# LEDs.net
KiCad netlist of a schematic drawn in Altium Designer
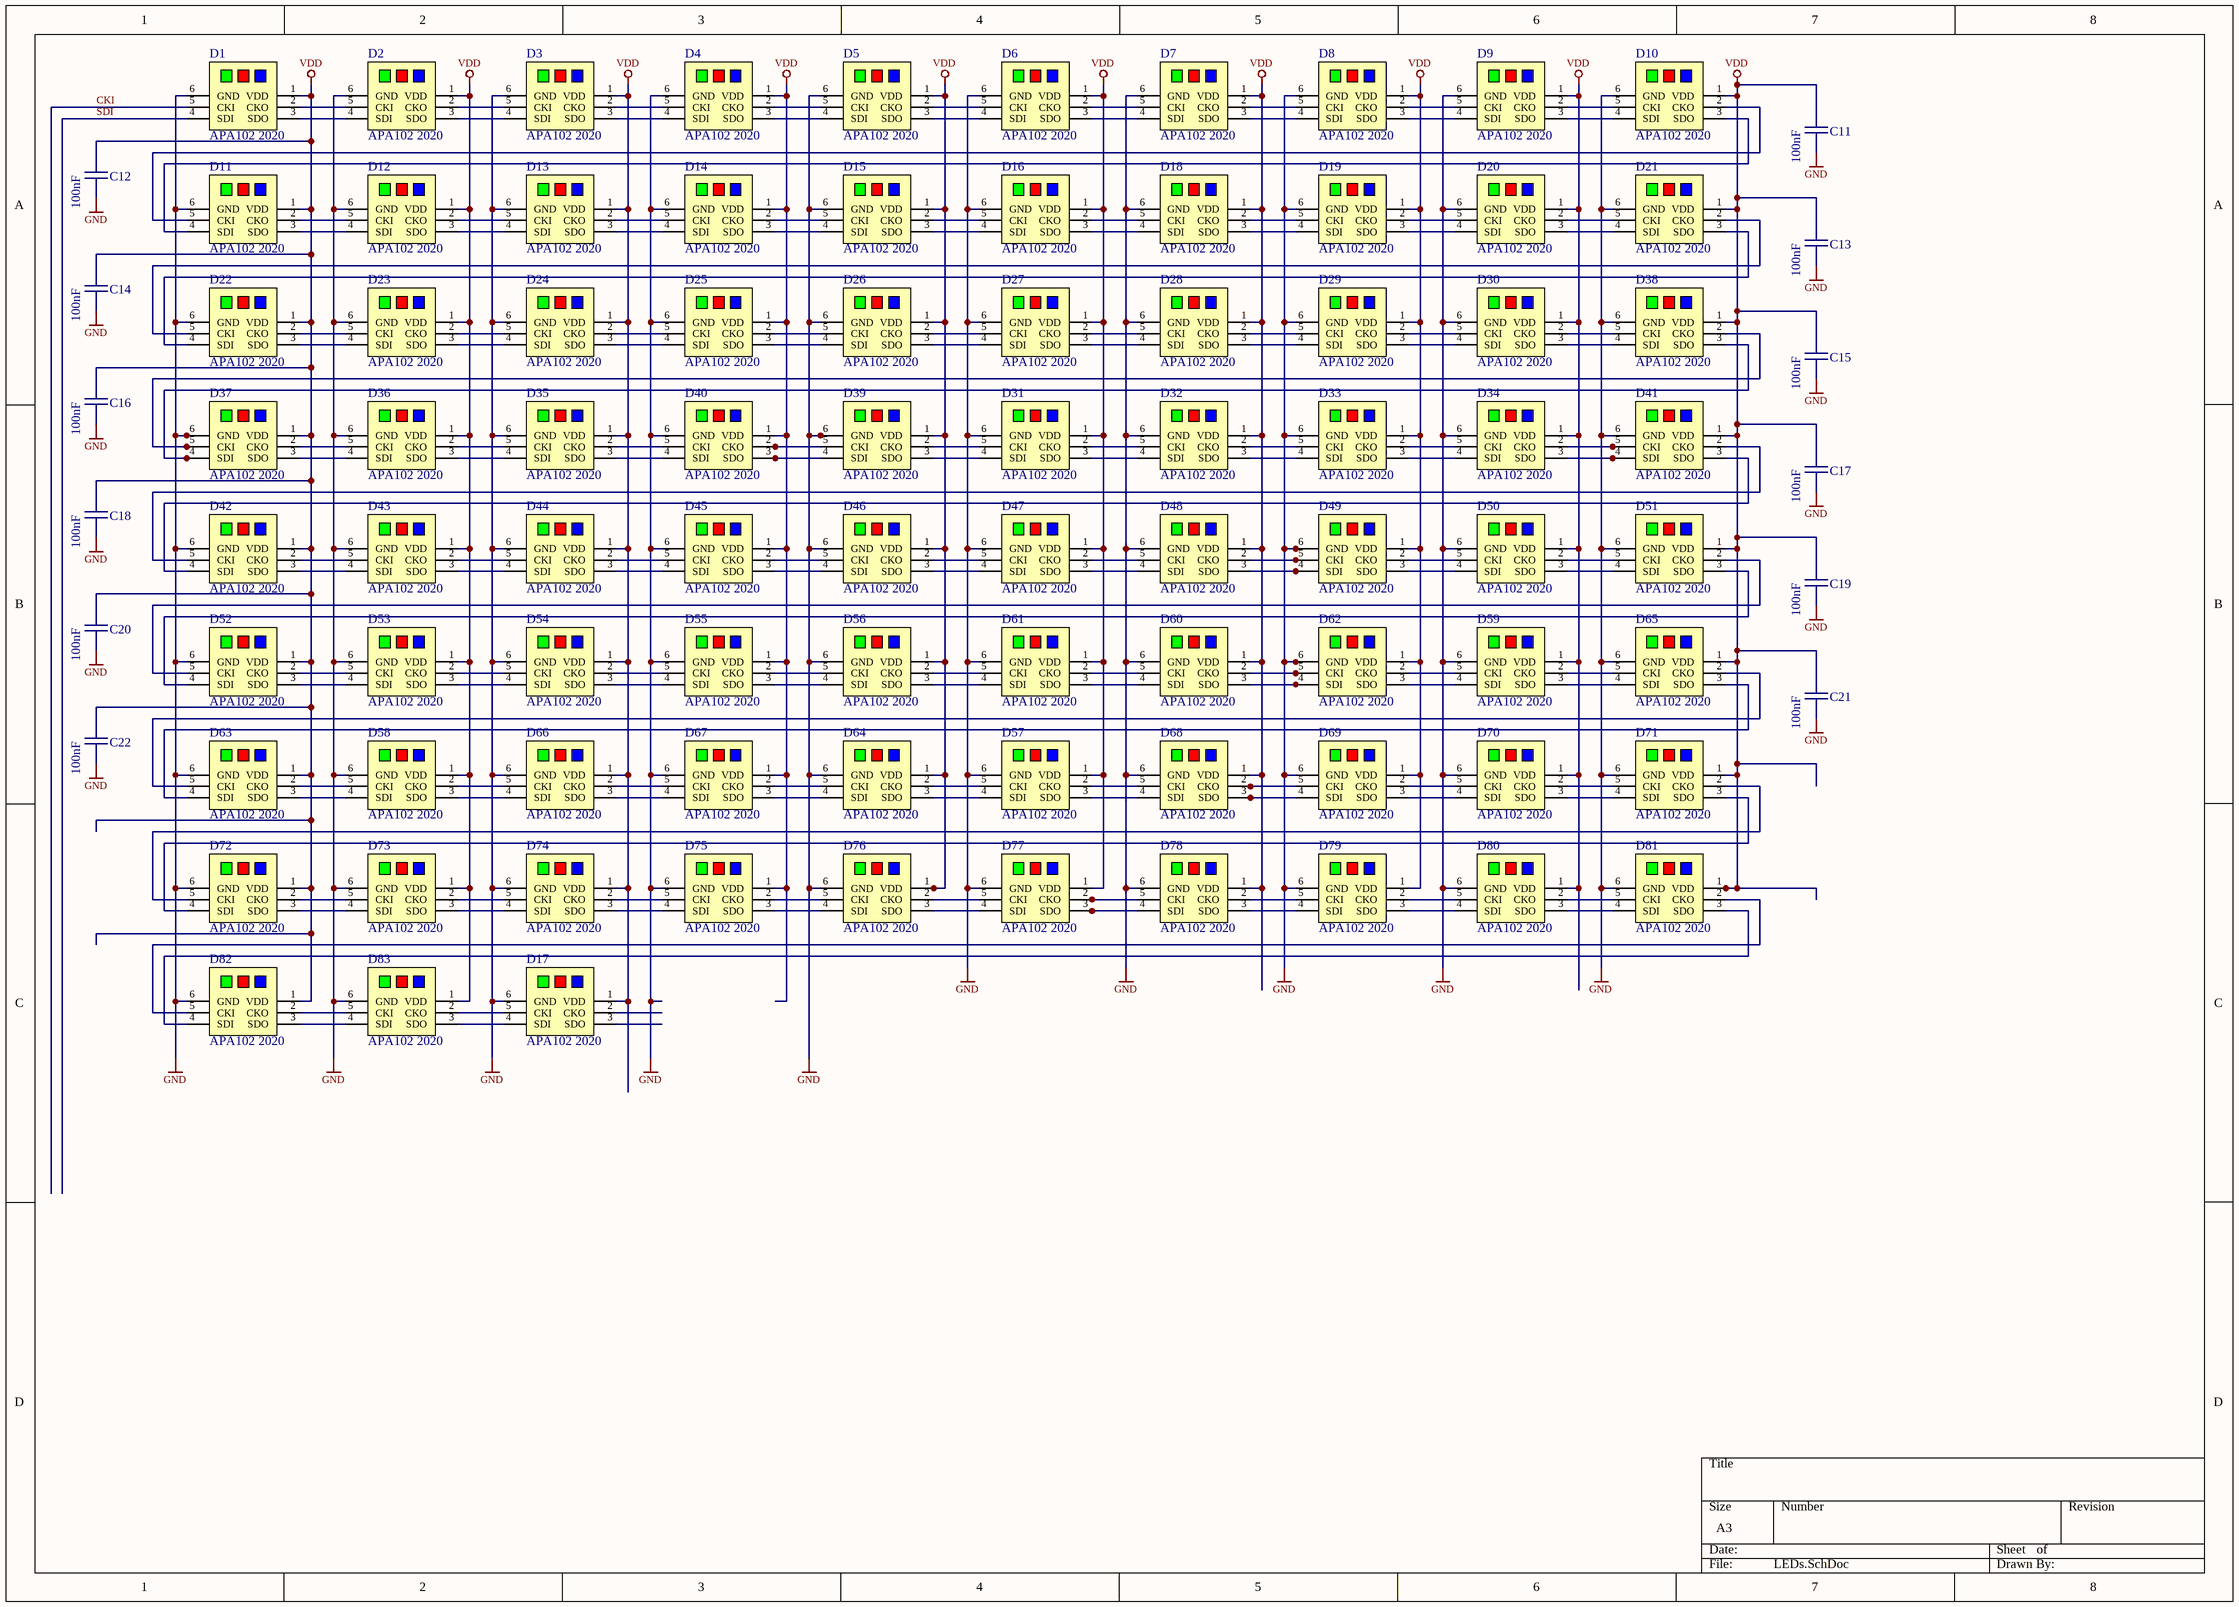
[diagram p0: LEDs.SchDoc]

(export (version "E")
  (design (tool "Eeschema 10.0.6"))
  (components
    (comp (ref "C11")
      (value "100nF")
      (footprint "CAPC0603(1608)55_N")
      (libsource (lib "OVLib_64") (part "CAP"))
    )
    (comp (ref "C12")
      (value "100nF")
      (footprint "CAPC0603(1608)55_N")
      (libsource (lib "OVLib_64") (part "CAP"))
    )
    (comp (ref "C13")
      (value "100nF")
      (footprint "CAPC0603(1608)55_N")
      (libsource (lib "OVLib_64") (part "CAP"))
    )
    (comp (ref "C14")
      (value "100nF")
      (footprint "CAPC0603(1608)55_N")
      (libsource (lib "OVLib_64") (part "CAP"))
    )
    (comp (ref "C15")
      (value "100nF")
      (footprint "CAPC0603(1608)55_N")
      (libsource (lib "OVLib_64") (part "CAP"))
    )
    (comp (ref "C16")
      (value "100nF")
      (footprint "CAPC0603(1608)55_N")
      (libsource (lib "OVLib_64") (part "CAP"))
    )
    (comp (ref "C17")
      (value "100nF")
      (footprint "CAPC0603(1608)55_N")
      (libsource (lib "OVLib_64") (part "CAP"))
    )
    (comp (ref "C18")
      (value "100nF")
      (footprint "CAPC0603(1608)55_N")
      (libsource (lib "OVLib_64") (part "CAP"))
    )
    (comp (ref "C19")
      (value "100nF")
      (footprint "CAPC0603(1608)55_N")
      (libsource (lib "OVLib_64") (part "CAP"))
    )
    (comp (ref "C20")
      (value "100nF")
      (footprint "CAPC0603(1608)55_N")
      (libsource (lib "OVLib_64") (part "CAP"))
    )
    (comp (ref "C21")
      (value "100nF")
      (footprint "CAPC0603(1608)55_N")
      (libsource (lib "OVLib_64") (part "CAP"))
    )
    (comp (ref "C22")
      (value "100nF")
      (footprint "CAPC0603(1608)55_N")
      (libsource (lib "OVLib_64") (part "CAP"))
    )
    (comp (ref "D1")
      (value "APA102 2020")
      (footprint "APA_RGB_LED_2020")
      (libsource (lib "OVLib_64") (part "LED_RGB_APA102"))
    )
    (comp (ref "D2")
      (value "APA102 2020")
      (footprint "APA_RGB_LED_2020")
      (libsource (lib "OVLib_64") (part "LED_RGB_APA102"))
    )
    (comp (ref "D3")
      (value "APA102 2020")
      (footprint "APA_RGB_LED_2020")
      (libsource (lib "OVLib_64") (part "LED_RGB_APA102"))
    )
    (comp (ref "D4")
      (value "APA102 2020")
      (footprint "APA_RGB_LED_2020")
      (libsource (lib "OVLib_64") (part "LED_RGB_APA102"))
    )
    (comp (ref "D5")
      (value "APA102 2020")
      (footprint "APA_RGB_LED_2020")
      (libsource (lib "OVLib_64") (part "LED_RGB_APA102"))
    )
    (comp (ref "D6")
      (value "APA102 2020")
      (footprint "APA_RGB_LED_2020")
      (libsource (lib "OVLib_64") (part "LED_RGB_APA102"))
    )
    (comp (ref "D7")
      (value "APA102 2020")
      (footprint "APA_RGB_LED_2020")
      (libsource (lib "OVLib_64") (part "LED_RGB_APA102"))
    )
    (comp (ref "D8")
      (value "APA102 2020")
      (footprint "APA_RGB_LED_2020")
      (libsource (lib "OVLib_64") (part "LED_RGB_APA102"))
    )
    (comp (ref "D9")
      (value "APA102 2020")
      (footprint "APA_RGB_LED_2020")
      (libsource (lib "OVLib_64") (part "LED_RGB_APA102"))
    )
    (comp (ref "D10")
      (value "APA102 2020")
      (footprint "APA_RGB_LED_2020")
      (libsource (lib "OVLib_64") (part "LED_RGB_APA102"))
    )
    (comp (ref "D11")
      (value "APA102 2020")
      (footprint "APA_RGB_LED_2020")
      (libsource (lib "OVLib_64") (part "LED_RGB_APA102"))
    )
    (comp (ref "D12")
      (value "APA102 2020")
      (footprint "APA_RGB_LED_2020")
      (libsource (lib "OVLib_64") (part "LED_RGB_APA102"))
    )
    (comp (ref "D13")
      (value "APA102 2020")
      (footprint "APA_RGB_LED_2020")
      (libsource (lib "OVLib_64") (part "LED_RGB_APA102"))
    )
    (comp (ref "D14")
      (value "APA102 2020")
      (footprint "APA_RGB_LED_2020")
      (libsource (lib "OVLib_64") (part "LED_RGB_APA102"))
    )
    (comp (ref "D15")
      (value "APA102 2020")
      (footprint "APA_RGB_LED_2020")
      (libsource (lib "OVLib_64") (part "LED_RGB_APA102"))
    )
    (comp (ref "D16")
      (value "APA102 2020")
      (footprint "APA_RGB_LED_2020")
      (libsource (lib "OVLib_64") (part "LED_RGB_APA102"))
    )
    (comp (ref "D17")
      (value "APA102 2020")
      (footprint "APA_RGB_LED_2020")
      (libsource (lib "OVLib_64") (part "LED_RGB_APA102"))
    )
    (comp (ref "D18")
      (value "APA102 2020")
      (footprint "APA_RGB_LED_2020")
      (libsource (lib "OVLib_64") (part "LED_RGB_APA102"))
    )
    (comp (ref "D19")
      (value "APA102 2020")
      (footprint "APA_RGB_LED_2020")
      (libsource (lib "OVLib_64") (part "LED_RGB_APA102"))
    )
    (comp (ref "D20")
      (value "APA102 2020")
      (footprint "APA_RGB_LED_2020")
      (libsource (lib "OVLib_64") (part "LED_RGB_APA102"))
    )
    (comp (ref "D21")
      (value "APA102 2020")
      (footprint "APA_RGB_LED_2020")
      (libsource (lib "OVLib_64") (part "LED_RGB_APA102"))
    )
    (comp (ref "D22")
      (value "APA102 2020")
      (footprint "APA_RGB_LED_2020")
      (libsource (lib "OVLib_64") (part "LED_RGB_APA102"))
    )
    (comp (ref "D23")
      (value "APA102 2020")
      (footprint "APA_RGB_LED_2020")
      (libsource (lib "OVLib_64") (part "LED_RGB_APA102"))
    )
    (comp (ref "D24")
      (value "APA102 2020")
      (footprint "APA_RGB_LED_2020")
      (libsource (lib "OVLib_64") (part "LED_RGB_APA102"))
    )
    (comp (ref "D25")
      (value "APA102 2020")
      (footprint "APA_RGB_LED_2020")
      (libsource (lib "OVLib_64") (part "LED_RGB_APA102"))
    )
    (comp (ref "D26")
      (value "APA102 2020")
      (footprint "APA_RGB_LED_2020")
      (libsource (lib "OVLib_64") (part "LED_RGB_APA102"))
    )
    (comp (ref "D27")
      (value "APA102 2020")
      (footprint "APA_RGB_LED_2020")
      (libsource (lib "OVLib_64") (part "LED_RGB_APA102"))
    )
    (comp (ref "D28")
      (value "APA102 2020")
      (footprint "APA_RGB_LED_2020")
      (libsource (lib "OVLib_64") (part "LED_RGB_APA102"))
    )
    (comp (ref "D29")
      (value "APA102 2020")
      (footprint "APA_RGB_LED_2020")
      (libsource (lib "OVLib_64") (part "LED_RGB_APA102"))
    )
    (comp (ref "D30")
      (value "APA102 2020")
      (footprint "APA_RGB_LED_2020")
      (libsource (lib "OVLib_64") (part "LED_RGB_APA102"))
    )
    (comp (ref "D31")
      (value "APA102 2020")
      (footprint "APA_RGB_LED_2020")
      (libsource (lib "OVLib_64") (part "LED_RGB_APA102"))
    )
    (comp (ref "D32")
      (value "APA102 2020")
      (footprint "APA_RGB_LED_2020")
      (libsource (lib "OVLib_64") (part "LED_RGB_APA102"))
    )
    (comp (ref "D33")
      (value "APA102 2020")
      (footprint "APA_RGB_LED_2020")
      (libsource (lib "OVLib_64") (part "LED_RGB_APA102"))
    )
    (comp (ref "D34")
      (value "APA102 2020")
      (footprint "APA_RGB_LED_2020")
      (libsource (lib "OVLib_64") (part "LED_RGB_APA102"))
    )
    (comp (ref "D35")
      (value "APA102 2020")
      (footprint "APA_RGB_LED_2020")
      (libsource (lib "OVLib_64") (part "LED_RGB_APA102"))
    )
    (comp (ref "D36")
      (value "APA102 2020")
      (footprint "APA_RGB_LED_2020")
      (libsource (lib "OVLib_64") (part "LED_RGB_APA102"))
    )
    (comp (ref "D37")
      (value "APA102 2020")
      (footprint "APA_RGB_LED_2020")
      (libsource (lib "OVLib_64") (part "LED_RGB_APA102"))
    )
    (comp (ref "D38")
      (value "APA102 2020")
      (footprint "APA_RGB_LED_2020")
      (libsource (lib "OVLib_64") (part "LED_RGB_APA102"))
    )
    (comp (ref "D39")
      (value "APA102 2020")
      (footprint "APA_RGB_LED_2020")
      (libsource (lib "OVLib_64") (part "LED_RGB_APA102"))
    )
    (comp (ref "D40")
      (value "APA102 2020")
      (footprint "APA_RGB_LED_2020")
      (libsource (lib "OVLib_64") (part "LED_RGB_APA102"))
    )
    (comp (ref "D41")
      (value "APA102 2020")
      (footprint "APA_RGB_LED_2020")
      (libsource (lib "OVLib_64") (part "LED_RGB_APA102"))
    )
    (comp (ref "D42")
      (value "APA102 2020")
      (footprint "APA_RGB_LED_2020")
      (libsource (lib "OVLib_64") (part "LED_RGB_APA102"))
    )
    (comp (ref "D43")
      (value "APA102 2020")
      (footprint "APA_RGB_LED_2020")
      (libsource (lib "OVLib_64") (part "LED_RGB_APA102"))
    )
    (comp (ref "D44")
      (value "APA102 2020")
      (footprint "APA_RGB_LED_2020")
      (libsource (lib "OVLib_64") (part "LED_RGB_APA102"))
    )
    (comp (ref "D45")
      (value "APA102 2020")
      (footprint "APA_RGB_LED_2020")
      (libsource (lib "OVLib_64") (part "LED_RGB_APA102"))
    )
    (comp (ref "D46")
      (value "APA102 2020")
      (footprint "APA_RGB_LED_2020")
      (libsource (lib "OVLib_64") (part "LED_RGB_APA102"))
    )
    (comp (ref "D47")
      (value "APA102 2020")
      (footprint "APA_RGB_LED_2020")
      (libsource (lib "OVLib_64") (part "LED_RGB_APA102"))
    )
    (comp (ref "D48")
      (value "APA102 2020")
      (footprint "APA_RGB_LED_2020")
      (libsource (lib "OVLib_64") (part "LED_RGB_APA102"))
    )
    (comp (ref "D49")
      (value "APA102 2020")
      (footprint "APA_RGB_LED_2020")
      (libsource (lib "OVLib_64") (part "LED_RGB_APA102"))
    )
    (comp (ref "D50")
      (value "APA102 2020")
      (footprint "APA_RGB_LED_2020")
      (libsource (lib "OVLib_64") (part "LED_RGB_APA102"))
    )
    (comp (ref "D51")
      (value "APA102 2020")
      (footprint "APA_RGB_LED_2020")
      (libsource (lib "OVLib_64") (part "LED_RGB_APA102"))
    )
    (comp (ref "D52")
      (value "APA102 2020")
      (footprint "APA_RGB_LED_2020")
      (libsource (lib "OVLib_64") (part "LED_RGB_APA102"))
    )
    (comp (ref "D53")
      (value "APA102 2020")
      (footprint "APA_RGB_LED_2020")
      (libsource (lib "OVLib_64") (part "LED_RGB_APA102"))
    )
    (comp (ref "D54")
      (value "APA102 2020")
      (footprint "APA_RGB_LED_2020")
      (libsource (lib "OVLib_64") (part "LED_RGB_APA102"))
    )
    (comp (ref "D55")
      (value "APA102 2020")
      (footprint "APA_RGB_LED_2020")
      (libsource (lib "OVLib_64") (part "LED_RGB_APA102"))
    )
    (comp (ref "D56")
      (value "APA102 2020")
      (footprint "APA_RGB_LED_2020")
      (libsource (lib "OVLib_64") (part "LED_RGB_APA102"))
    )
    (comp (ref "D57")
      (value "APA102 2020")
      (footprint "APA_RGB_LED_2020")
      (libsource (lib "OVLib_64") (part "LED_RGB_APA102"))
    )
    (comp (ref "D58")
      (value "APA102 2020")
      (footprint "APA_RGB_LED_2020")
      (libsource (lib "OVLib_64") (part "LED_RGB_APA102"))
    )
    (comp (ref "D59")
      (value "APA102 2020")
      (footprint "APA_RGB_LED_2020")
      (libsource (lib "OVLib_64") (part "LED_RGB_APA102"))
    )
    (comp (ref "D60")
      (value "APA102 2020")
      (footprint "APA_RGB_LED_2020")
      (libsource (lib "OVLib_64") (part "LED_RGB_APA102"))
    )
    (comp (ref "D61")
      (value "APA102 2020")
      (footprint "APA_RGB_LED_2020")
      (libsource (lib "OVLib_64") (part "LED_RGB_APA102"))
    )
    (comp (ref "D62")
      (value "APA102 2020")
      (footprint "APA_RGB_LED_2020")
      (libsource (lib "OVLib_64") (part "LED_RGB_APA102"))
    )
    (comp (ref "D63")
      (value "APA102 2020")
      (footprint "APA_RGB_LED_2020")
      (libsource (lib "OVLib_64") (part "LED_RGB_APA102"))
    )
    (comp (ref "D64")
      (value "APA102 2020")
      (footprint "APA_RGB_LED_2020")
      (libsource (lib "OVLib_64") (part "LED_RGB_APA102"))
    )
    (comp (ref "D65")
      (value "APA102 2020")
      (footprint "APA_RGB_LED_2020")
      (libsource (lib "OVLib_64") (part "LED_RGB_APA102"))
    )
    (comp (ref "D66")
      (value "APA102 2020")
      (footprint "APA_RGB_LED_2020")
      (libsource (lib "OVLib_64") (part "LED_RGB_APA102"))
    )
    (comp (ref "D67")
      (value "APA102 2020")
      (footprint "APA_RGB_LED_2020")
      (libsource (lib "OVLib_64") (part "LED_RGB_APA102"))
    )
    (comp (ref "D68")
      (value "APA102 2020")
      (footprint "APA_RGB_LED_2020")
      (libsource (lib "OVLib_64") (part "LED_RGB_APA102"))
    )
    (comp (ref "D69")
      (value "APA102 2020")
      (footprint "APA_RGB_LED_2020")
      (libsource (lib "OVLib_64") (part "LED_RGB_APA102"))
    )
    (comp (ref "D70")
      (value "APA102 2020")
      (footprint "APA_RGB_LED_2020")
      (libsource (lib "OVLib_64") (part "LED_RGB_APA102"))
    )
    (comp (ref "D71")
      (value "APA102 2020")
      (footprint "APA_RGB_LED_2020")
      (libsource (lib "OVLib_64") (part "LED_RGB_APA102"))
    )
    (comp (ref "D72")
      (value "APA102 2020")
      (footprint "APA_RGB_LED_2020")
      (libsource (lib "OVLib_64") (part "LED_RGB_APA102"))
    )
    (comp (ref "D73")
      (value "APA102 2020")
      (footprint "APA_RGB_LED_2020")
      (libsource (lib "OVLib_64") (part "LED_RGB_APA102"))
    )
    (comp (ref "D74")
      (value "APA102 2020")
      (footprint "APA_RGB_LED_2020")
      (libsource (lib "OVLib_64") (part "LED_RGB_APA102"))
    )
    (comp (ref "D75")
      (value "APA102 2020")
      (footprint "APA_RGB_LED_2020")
      (libsource (lib "OVLib_64") (part "LED_RGB_APA102"))
    )
    (comp (ref "D76")
      (value "APA102 2020")
      (footprint "APA_RGB_LED_2020")
      (libsource (lib "OVLib_64") (part "LED_RGB_APA102"))
    )
    (comp (ref "D77")
      (value "APA102 2020")
      (footprint "APA_RGB_LED_2020")
      (libsource (lib "OVLib_64") (part "LED_RGB_APA102"))
    )
    (comp (ref "D78")
      (value "APA102 2020")
      (footprint "APA_RGB_LED_2020")
      (libsource (lib "OVLib_64") (part "LED_RGB_APA102"))
    )
    (comp (ref "D79")
      (value "APA102 2020")
      (footprint "APA_RGB_LED_2020")
      (libsource (lib "OVLib_64") (part "LED_RGB_APA102"))
    )
    (comp (ref "D80")
      (value "APA102 2020")
      (footprint "APA_RGB_LED_2020")
      (libsource (lib "OVLib_64") (part "LED_RGB_APA102"))
    )
    (comp (ref "D81")
      (value "APA102 2020")
      (footprint "APA_RGB_LED_2020")
      (libsource (lib "OVLib_64") (part "LED_RGB_APA102"))
    )
    (comp (ref "D82")
      (value "APA102 2020")
      (footprint "APA_RGB_LED_2020")
      (libsource (lib "OVLib_64") (part "LED_RGB_APA102"))
    )
    (comp (ref "D83")
      (value "APA102 2020")
      (footprint "APA_RGB_LED_2020")
      (libsource (lib "OVLib_64") (part "LED_RGB_APA102"))
    )
  )
  (nets
    (net (code "1") (name "/CKI") (class "Default")
      (node (ref "D1") (pin "5") (pinfunction "CKI_5") (pintype "passive"))
    )
    (net (code "2") (name "/SDI") (class "Default")
      (node (ref "D1") (pin "4") (pinfunction "SDI_4") (pintype "passive"))
    )
    (net (code "3") (name "GND") (class "Default")
      (node (ref "C11") (pin "1") (pinfunction "1_1") (pintype "passive"))
      (node (ref "C12") (pin "1") (pinfunction "1_1") (pintype "passive"))
      (node (ref "C13") (pin "1") (pinfunction "1_1") (pintype "passive"))
      (node (ref "C14") (pin "1") (pinfunction "1_1") (pintype "passive"))
      (node (ref "C15") (pin "1") (pinfunction "1_1") (pintype "passive"))
      (node (ref "C16") (pin "1") (pinfunction "1_1") (pintype "passive"))
      (node (ref "C17") (pin "1") (pinfunction "1_1") (pintype "passive"))
      (node (ref "C18") (pin "1") (pinfunction "1_1") (pintype "passive"))
      (node (ref "C19") (pin "1") (pinfunction "1_1") (pintype "passive"))
      (node (ref "C20") (pin "1") (pinfunction "1_1") (pintype "passive"))
      (node (ref "C21") (pin "1") (pinfunction "1_1") (pintype "passive"))
      (node (ref "C22") (pin "1") (pinfunction "1_1") (pintype "passive"))
      (node (ref "D1") (pin "6") (pinfunction "GND_6") (pintype "passive"))
      (node (ref "D10") (pin "6") (pinfunction "GND_6") (pintype "passive"))
      (node (ref "D11") (pin "6") (pinfunction "GND_6") (pintype "passive"))
      (node (ref "D12") (pin "6") (pinfunction "GND_6") (pintype "passive"))
      (node (ref "D13") (pin "6") (pinfunction "GND_6") (pintype "passive"))
      (node (ref "D14") (pin "6") (pinfunction "GND_6") (pintype "passive"))
      (node (ref "D15") (pin "6") (pinfunction "GND_6") (pintype "passive"))
      (node (ref "D16") (pin "6") (pinfunction "GND_6") (pintype "passive"))
      (node (ref "D17") (pin "6") (pinfunction "GND_6") (pintype "passive"))
      (node (ref "D18") (pin "6") (pinfunction "GND_6") (pintype "passive"))
      (node (ref "D19") (pin "6") (pinfunction "GND_6") (pintype "passive"))
      (node (ref "D2") (pin "6") (pinfunction "GND_6") (pintype "passive"))
      (node (ref "D20") (pin "6") (pinfunction "GND_6") (pintype "passive"))
      (node (ref "D21") (pin "6") (pinfunction "GND_6") (pintype "passive"))
      (node (ref "D22") (pin "6") (pinfunction "GND_6") (pintype "passive"))
      (node (ref "D23") (pin "6") (pinfunction "GND_6") (pintype "passive"))
      (node (ref "D24") (pin "6") (pinfunction "GND_6") (pintype "passive"))
      (node (ref "D25") (pin "6") (pinfunction "GND_6") (pintype "passive"))
      (node (ref "D26") (pin "6") (pinfunction "GND_6") (pintype "passive"))
      (node (ref "D27") (pin "6") (pinfunction "GND_6") (pintype "passive"))
      (node (ref "D28") (pin "6") (pinfunction "GND_6") (pintype "passive"))
      (node (ref "D29") (pin "6") (pinfunction "GND_6") (pintype "passive"))
      (node (ref "D3") (pin "6") (pinfunction "GND_6") (pintype "passive"))
      (node (ref "D30") (pin "6") (pinfunction "GND_6") (pintype "passive"))
      (node (ref "D31") (pin "6") (pinfunction "GND_6") (pintype "passive"))
      (node (ref "D32") (pin "6") (pinfunction "GND_6") (pintype "passive"))
      (node (ref "D33") (pin "6") (pinfunction "GND_6") (pintype "passive"))
      (node (ref "D34") (pin "6") (pinfunction "GND_6") (pintype "passive"))
      (node (ref "D35") (pin "6") (pinfunction "GND_6") (pintype "passive"))
      (node (ref "D36") (pin "6") (pinfunction "GND_6") (pintype "passive"))
      (node (ref "D37") (pin "6") (pinfunction "GND_6") (pintype "passive"))
      (node (ref "D38") (pin "6") (pinfunction "GND_6") (pintype "passive"))
      (node (ref "D39") (pin "6") (pinfunction "GND_6") (pintype "passive"))
      (node (ref "D4") (pin "6") (pinfunction "GND_6") (pintype "passive"))
      (node (ref "D40") (pin "6") (pinfunction "GND_6") (pintype "passive"))
      (node (ref "D41") (pin "6") (pinfunction "GND_6") (pintype "passive"))
      (node (ref "D42") (pin "6") (pinfunction "GND_6") (pintype "passive"))
      (node (ref "D43") (pin "6") (pinfunction "GND_6") (pintype "passive"))
      (node (ref "D44") (pin "6") (pinfunction "GND_6") (pintype "passive"))
      (node (ref "D45") (pin "6") (pinfunction "GND_6") (pintype "passive"))
      (node (ref "D46") (pin "6") (pinfunction "GND_6") (pintype "passive"))
      (node (ref "D47") (pin "6") (pinfunction "GND_6") (pintype "passive"))
      (node (ref "D48") (pin "6") (pinfunction "GND_6") (pintype "passive"))
      (node (ref "D49") (pin "6") (pinfunction "GND_6") (pintype "passive"))
      (node (ref "D5") (pin "6") (pinfunction "GND_6") (pintype "passive"))
      (node (ref "D50") (pin "6") (pinfunction "GND_6") (pintype "passive"))
      (node (ref "D51") (pin "6") (pinfunction "GND_6") (pintype "passive"))
      (node (ref "D52") (pin "6") (pinfunction "GND_6") (pintype "passive"))
      (node (ref "D53") (pin "6") (pinfunction "GND_6") (pintype "passive"))
      (node (ref "D54") (pin "6") (pinfunction "GND_6") (pintype "passive"))
      (node (ref "D55") (pin "6") (pinfunction "GND_6") (pintype "passive"))
      (node (ref "D56") (pin "6") (pinfunction "GND_6") (pintype "passive"))
      (node (ref "D57") (pin "6") (pinfunction "GND_6") (pintype "passive"))
      (node (ref "D58") (pin "6") (pinfunction "GND_6") (pintype "passive"))
      (node (ref "D59") (pin "6") (pinfunction "GND_6") (pintype "passive"))
      (node (ref "D6") (pin "6") (pinfunction "GND_6") (pintype "passive"))
      (node (ref "D60") (pin "6") (pinfunction "GND_6") (pintype "passive"))
      (node (ref "D61") (pin "6") (pinfunction "GND_6") (pintype "passive"))
      (node (ref "D62") (pin "6") (pinfunction "GND_6") (pintype "passive"))
      (node (ref "D63") (pin "6") (pinfunction "GND_6") (pintype "passive"))
      (node (ref "D64") (pin "6") (pinfunction "GND_6") (pintype "passive"))
      (node (ref "D65") (pin "6") (pinfunction "GND_6") (pintype "passive"))
      (node (ref "D66") (pin "6") (pinfunction "GND_6") (pintype "passive"))
      (node (ref "D67") (pin "6") (pinfunction "GND_6") (pintype "passive"))
      (node (ref "D68") (pin "6") (pinfunction "GND_6") (pintype "passive"))
      (node (ref "D69") (pin "6") (pinfunction "GND_6") (pintype "passive"))
      (node (ref "D7") (pin "6") (pinfunction "GND_6") (pintype "passive"))
      (node (ref "D70") (pin "6") (pinfunction "GND_6") (pintype "passive"))
      (node (ref "D71") (pin "6") (pinfunction "GND_6") (pintype "passive"))
      (node (ref "D72") (pin "6") (pinfunction "GND_6") (pintype "passive"))
      (node (ref "D73") (pin "6") (pinfunction "GND_6") (pintype "passive"))
      (node (ref "D74") (pin "6") (pinfunction "GND_6") (pintype "passive"))
      (node (ref "D75") (pin "6") (pinfunction "GND_6") (pintype "passive"))
      (node (ref "D76") (pin "6") (pinfunction "GND_6") (pintype "passive"))
      (node (ref "D77") (pin "6") (pinfunction "GND_6") (pintype "passive"))
      (node (ref "D78") (pin "6") (pinfunction "GND_6") (pintype "passive"))
      (node (ref "D79") (pin "6") (pinfunction "GND_6") (pintype "passive"))
      (node (ref "D8") (pin "6") (pinfunction "GND_6") (pintype "passive"))
      (node (ref "D80") (pin "6") (pinfunction "GND_6") (pintype "passive"))
      (node (ref "D81") (pin "6") (pinfunction "GND_6") (pintype "passive"))
      (node (ref "D82") (pin "6") (pinfunction "GND_6") (pintype "passive"))
      (node (ref "D83") (pin "6") (pinfunction "GND_6") (pintype "passive"))
      (node (ref "D9") (pin "6") (pinfunction "GND_6") (pintype "passive"))
    )
    (net (code "4") (name "Net-(D1-CKO)") (class "Default")
      (node (ref "D1") (pin "2") (pinfunction "CKO_2") (pintype "passive"))
      (node (ref "D2") (pin "5") (pinfunction "CKI_5") (pintype "passive"))
    )
    (net (code "5") (name "Net-(D1-SDO)") (class "Default")
      (node (ref "D1") (pin "3") (pinfunction "SDO_3") (pintype "passive"))
      (node (ref "D2") (pin "4") (pinfunction "SDI_4") (pintype "passive"))
    )
    (net (code "6") (name "Net-(D2-CKO)") (class "Default")
      (node (ref "D2") (pin "2") (pinfunction "CKO_2") (pintype "passive"))
      (node (ref "D3") (pin "5") (pinfunction "CKI_5") (pintype "passive"))
    )
    (net (code "7") (name "Net-(D2-SDO)") (class "Default")
      (node (ref "D2") (pin "3") (pinfunction "SDO_3") (pintype "passive"))
      (node (ref "D3") (pin "4") (pinfunction "SDI_4") (pintype "passive"))
    )
    (net (code "8") (name "Net-(D3-CKO)") (class "Default")
      (node (ref "D3") (pin "2") (pinfunction "CKO_2") (pintype "passive"))
      (node (ref "D4") (pin "5") (pinfunction "CKI_5") (pintype "passive"))
    )
    (net (code "9") (name "Net-(D3-SDO)") (class "Default")
      (node (ref "D3") (pin "3") (pinfunction "SDO_3") (pintype "passive"))
      (node (ref "D4") (pin "4") (pinfunction "SDI_4") (pintype "passive"))
    )
    (net (code "10") (name "Net-(D4-CKO)") (class "Default")
      (node (ref "D4") (pin "2") (pinfunction "CKO_2") (pintype "passive"))
      (node (ref "D5") (pin "5") (pinfunction "CKI_5") (pintype "passive"))
    )
    (net (code "11") (name "Net-(D4-SDO)") (class "Default")
      (node (ref "D4") (pin "3") (pinfunction "SDO_3") (pintype "passive"))
      (node (ref "D5") (pin "4") (pinfunction "SDI_4") (pintype "passive"))
    )
    (net (code "12") (name "Net-(D5-CKO)") (class "Default")
      (node (ref "D5") (pin "2") (pinfunction "CKO_2") (pintype "passive"))
      (node (ref "D6") (pin "5") (pinfunction "CKI_5") (pintype "passive"))
    )
    (net (code "13") (name "Net-(D5-SDO)") (class "Default")
      (node (ref "D5") (pin "3") (pinfunction "SDO_3") (pintype "passive"))
      (node (ref "D6") (pin "4") (pinfunction "SDI_4") (pintype "passive"))
    )
    (net (code "14") (name "Net-(D6-CKO)") (class "Default")
      (node (ref "D6") (pin "2") (pinfunction "CKO_2") (pintype "passive"))
      (node (ref "D7") (pin "5") (pinfunction "CKI_5") (pintype "passive"))
    )
    (net (code "15") (name "Net-(D6-SDO)") (class "Default")
      (node (ref "D6") (pin "3") (pinfunction "SDO_3") (pintype "passive"))
      (node (ref "D7") (pin "4") (pinfunction "SDI_4") (pintype "passive"))
    )
    (net (code "16") (name "Net-(D7-CKO)") (class "Default")
      (node (ref "D7") (pin "2") (pinfunction "CKO_2") (pintype "passive"))
      (node (ref "D8") (pin "5") (pinfunction "CKI_5") (pintype "passive"))
    )
    (net (code "17") (name "Net-(D7-SDO)") (class "Default")
      (node (ref "D7") (pin "3") (pinfunction "SDO_3") (pintype "passive"))
      (node (ref "D8") (pin "4") (pinfunction "SDI_4") (pintype "passive"))
    )
    (net (code "18") (name "Net-(D8-CKO)") (class "Default")
      (node (ref "D8") (pin "2") (pinfunction "CKO_2") (pintype "passive"))
      (node (ref "D9") (pin "5") (pinfunction "CKI_5") (pintype "passive"))
    )
    (net (code "19") (name "Net-(D8-SDO)") (class "Default")
      (node (ref "D8") (pin "3") (pinfunction "SDO_3") (pintype "passive"))
      (node (ref "D9") (pin "4") (pinfunction "SDI_4") (pintype "passive"))
    )
    (net (code "20") (name "Net-(D10-CKI)") (class "Default")
      (node (ref "D10") (pin "5") (pinfunction "CKI_5") (pintype "passive"))
      (node (ref "D9") (pin "2") (pinfunction "CKO_2") (pintype "passive"))
    )
    (net (code "21") (name "Net-(D10-CKO)") (class "Default")
      (node (ref "D10") (pin "2") (pinfunction "CKO_2") (pintype "passive"))
      (node (ref "D11") (pin "5") (pinfunction "CKI_5") (pintype "passive"))
    )
    (net (code "22") (name "Net-(D10-SDI)") (class "Default")
      (node (ref "D10") (pin "4") (pinfunction "SDI_4") (pintype "passive"))
      (node (ref "D9") (pin "3") (pinfunction "SDO_3") (pintype "passive"))
    )
    (net (code "23") (name "Net-(D10-SDO)") (class "Default")
      (node (ref "D10") (pin "3") (pinfunction "SDO_3") (pintype "passive"))
      (node (ref "D11") (pin "4") (pinfunction "SDI_4") (pintype "passive"))
    )
    (net (code "24") (name "Net-(D11-CKO)") (class "Default")
      (node (ref "D11") (pin "2") (pinfunction "CKO_2") (pintype "passive"))
      (node (ref "D12") (pin "5") (pinfunction "CKI_5") (pintype "passive"))
    )
    (net (code "25") (name "Net-(D11-SDO)") (class "Default")
      (node (ref "D11") (pin "3") (pinfunction "SDO_3") (pintype "passive"))
      (node (ref "D12") (pin "4") (pinfunction "SDI_4") (pintype "passive"))
    )
    (net (code "26") (name "Net-(D12-CKO)") (class "Default")
      (node (ref "D12") (pin "2") (pinfunction "CKO_2") (pintype "passive"))
      (node (ref "D13") (pin "5") (pinfunction "CKI_5") (pintype "passive"))
    )
    (net (code "27") (name "Net-(D12-SDO)") (class "Default")
      (node (ref "D12") (pin "3") (pinfunction "SDO_3") (pintype "passive"))
      (node (ref "D13") (pin "4") (pinfunction "SDI_4") (pintype "passive"))
    )
    (net (code "28") (name "Net-(D13-CKO)") (class "Default")
      (node (ref "D13") (pin "2") (pinfunction "CKO_2") (pintype "passive"))
      (node (ref "D14") (pin "5") (pinfunction "CKI_5") (pintype "passive"))
    )
    (net (code "29") (name "Net-(D13-SDO)") (class "Default")
      (node (ref "D13") (pin "3") (pinfunction "SDO_3") (pintype "passive"))
      (node (ref "D14") (pin "4") (pinfunction "SDI_4") (pintype "passive"))
    )
    (net (code "30") (name "Net-(D14-CKO)") (class "Default")
      (node (ref "D14") (pin "2") (pinfunction "CKO_2") (pintype "passive"))
      (node (ref "D15") (pin "5") (pinfunction "CKI_5") (pintype "passive"))
    )
    (net (code "31") (name "Net-(D14-SDO)") (class "Default")
      (node (ref "D14") (pin "3") (pinfunction "SDO_3") (pintype "passive"))
      (node (ref "D15") (pin "4") (pinfunction "SDI_4") (pintype "passive"))
    )
    (net (code "32") (name "Net-(D15-CKO)") (class "Default")
      (node (ref "D15") (pin "2") (pinfunction "CKO_2") (pintype "passive"))
      (node (ref "D16") (pin "5") (pinfunction "CKI_5") (pintype "passive"))
    )
    (net (code "33") (name "Net-(D15-SDO)") (class "Default")
      (node (ref "D15") (pin "3") (pinfunction "SDO_3") (pintype "passive"))
      (node (ref "D16") (pin "4") (pinfunction "SDI_4") (pintype "passive"))
    )
    (net (code "34") (name "Net-(D16-CKO)") (class "Default")
      (node (ref "D16") (pin "2") (pinfunction "CKO_2") (pintype "passive"))
      (node (ref "D18") (pin "5") (pinfunction "CKI_5") (pintype "passive"))
    )
    (net (code "35") (name "Net-(D16-SDO)") (class "Default")
      (node (ref "D16") (pin "3") (pinfunction "SDO_3") (pintype "passive"))
      (node (ref "D18") (pin "4") (pinfunction "SDI_4") (pintype "passive"))
    )
    (net (code "36") (name "Net-(D17-CKI)") (class "Default")
      (node (ref "D17") (pin "5") (pinfunction "CKI_5") (pintype "passive"))
      (node (ref "D83") (pin "2") (pinfunction "CKO_2") (pintype "passive"))
    )
    (net (code "37") (name "Net-(D17-SDI)") (class "Default")
      (node (ref "D17") (pin "4") (pinfunction "SDI_4") (pintype "passive"))
      (node (ref "D83") (pin "3") (pinfunction "SDO_3") (pintype "passive"))
    )
    (net (code "38") (name "Net-(D18-CKO)") (class "Default")
      (node (ref "D18") (pin "2") (pinfunction "CKO_2") (pintype "passive"))
      (node (ref "D19") (pin "5") (pinfunction "CKI_5") (pintype "passive"))
    )
    (net (code "39") (name "Net-(D18-SDO)") (class "Default")
      (node (ref "D18") (pin "3") (pinfunction "SDO_3") (pintype "passive"))
      (node (ref "D19") (pin "4") (pinfunction "SDI_4") (pintype "passive"))
    )
    (net (code "40") (name "Net-(D19-CKO)") (class "Default")
      (node (ref "D19") (pin "2") (pinfunction "CKO_2") (pintype "passive"))
      (node (ref "D20") (pin "5") (pinfunction "CKI_5") (pintype "passive"))
    )
    (net (code "41") (name "Net-(D19-SDO)") (class "Default")
      (node (ref "D19") (pin "3") (pinfunction "SDO_3") (pintype "passive"))
      (node (ref "D20") (pin "4") (pinfunction "SDI_4") (pintype "passive"))
    )
    (net (code "42") (name "Net-(D20-CKO)") (class "Default")
      (node (ref "D20") (pin "2") (pinfunction "CKO_2") (pintype "passive"))
      (node (ref "D21") (pin "5") (pinfunction "CKI_5") (pintype "passive"))
    )
    (net (code "43") (name "Net-(D20-SDO)") (class "Default")
      (node (ref "D20") (pin "3") (pinfunction "SDO_3") (pintype "passive"))
      (node (ref "D21") (pin "4") (pinfunction "SDI_4") (pintype "passive"))
    )
    (net (code "44") (name "Net-(D21-CKO)") (class "Default")
      (node (ref "D21") (pin "2") (pinfunction "CKO_2") (pintype "passive"))
      (node (ref "D22") (pin "5") (pinfunction "CKI_5") (pintype "passive"))
    )
    (net (code "45") (name "Net-(D21-SDO)") (class "Default")
      (node (ref "D21") (pin "3") (pinfunction "SDO_3") (pintype "passive"))
      (node (ref "D22") (pin "4") (pinfunction "SDI_4") (pintype "passive"))
    )
    (net (code "46") (name "Net-(D22-CKO)") (class "Default")
      (node (ref "D22") (pin "2") (pinfunction "CKO_2") (pintype "passive"))
      (node (ref "D23") (pin "5") (pinfunction "CKI_5") (pintype "passive"))
    )
    (net (code "47") (name "Net-(D22-SDO)") (class "Default")
      (node (ref "D22") (pin "3") (pinfunction "SDO_3") (pintype "passive"))
      (node (ref "D23") (pin "4") (pinfunction "SDI_4") (pintype "passive"))
    )
    (net (code "48") (name "Net-(D23-CKO)") (class "Default")
      (node (ref "D23") (pin "2") (pinfunction "CKO_2") (pintype "passive"))
      (node (ref "D24") (pin "5") (pinfunction "CKI_5") (pintype "passive"))
    )
    (net (code "49") (name "Net-(D23-SDO)") (class "Default")
      (node (ref "D23") (pin "3") (pinfunction "SDO_3") (pintype "passive"))
      (node (ref "D24") (pin "4") (pinfunction "SDI_4") (pintype "passive"))
    )
    (net (code "50") (name "Net-(D24-CKO)") (class "Default")
      (node (ref "D24") (pin "2") (pinfunction "CKO_2") (pintype "passive"))
      (node (ref "D25") (pin "5") (pinfunction "CKI_5") (pintype "passive"))
    )
    (net (code "51") (name "Net-(D24-SDO)") (class "Default")
      (node (ref "D24") (pin "3") (pinfunction "SDO_3") (pintype "passive"))
      (node (ref "D25") (pin "4") (pinfunction "SDI_4") (pintype "passive"))
    )
    (net (code "52") (name "Net-(D25-CKO)") (class "Default")
      (node (ref "D25") (pin "2") (pinfunction "CKO_2") (pintype "passive"))
      (node (ref "D26") (pin "5") (pinfunction "CKI_5") (pintype "passive"))
    )
    (net (code "53") (name "Net-(D25-SDO)") (class "Default")
      (node (ref "D25") (pin "3") (pinfunction "SDO_3") (pintype "passive"))
      (node (ref "D26") (pin "4") (pinfunction "SDI_4") (pintype "passive"))
    )
    (net (code "54") (name "Net-(D26-CKO)") (class "Default")
      (node (ref "D26") (pin "2") (pinfunction "CKO_2") (pintype "passive"))
      (node (ref "D27") (pin "5") (pinfunction "CKI_5") (pintype "passive"))
    )
    (net (code "55") (name "Net-(D26-SDO)") (class "Default")
      (node (ref "D26") (pin "3") (pinfunction "SDO_3") (pintype "passive"))
      (node (ref "D27") (pin "4") (pinfunction "SDI_4") (pintype "passive"))
    )
    (net (code "56") (name "Net-(D27-CKO)") (class "Default")
      (node (ref "D27") (pin "2") (pinfunction "CKO_2") (pintype "passive"))
      (node (ref "D28") (pin "5") (pinfunction "CKI_5") (pintype "passive"))
    )
    (net (code "57") (name "Net-(D27-SDO)") (class "Default")
      (node (ref "D27") (pin "3") (pinfunction "SDO_3") (pintype "passive"))
      (node (ref "D28") (pin "4") (pinfunction "SDI_4") (pintype "passive"))
    )
    (net (code "58") (name "Net-(D28-CKO)") (class "Default")
      (node (ref "D28") (pin "2") (pinfunction "CKO_2") (pintype "passive"))
      (node (ref "D29") (pin "5") (pinfunction "CKI_5") (pintype "passive"))
    )
    (net (code "59") (name "Net-(D28-SDO)") (class "Default")
      (node (ref "D28") (pin "3") (pinfunction "SDO_3") (pintype "passive"))
      (node (ref "D29") (pin "4") (pinfunction "SDI_4") (pintype "passive"))
    )
    (net (code "60") (name "Net-(D29-CKO)") (class "Default")
      (node (ref "D29") (pin "2") (pinfunction "CKO_2") (pintype "passive"))
      (node (ref "D30") (pin "5") (pinfunction "CKI_5") (pintype "passive"))
    )
    (net (code "61") (name "Net-(D29-SDO)") (class "Default")
      (node (ref "D29") (pin "3") (pinfunction "SDO_3") (pintype "passive"))
      (node (ref "D30") (pin "4") (pinfunction "SDI_4") (pintype "passive"))
    )
    (net (code "62") (name "Net-(D30-CKO)") (class "Default")
      (node (ref "D30") (pin "2") (pinfunction "CKO_2") (pintype "passive"))
      (node (ref "D38") (pin "5") (pinfunction "CKI_5") (pintype "passive"))
    )
    (net (code "63") (name "Net-(D30-SDO)") (class "Default")
      (node (ref "D30") (pin "3") (pinfunction "SDO_3") (pintype "passive"))
      (node (ref "D38") (pin "4") (pinfunction "SDI_4") (pintype "passive"))
    )
    (net (code "64") (name "Net-(D31-CKI)") (class "Default")
      (node (ref "D31") (pin "5") (pinfunction "CKI_5") (pintype "passive"))
      (node (ref "D39") (pin "2") (pinfunction "CKO_2") (pintype "passive"))
    )
    (net (code "65") (name "Net-(D31-CKO)") (class "Default")
      (node (ref "D31") (pin "2") (pinfunction "CKO_2") (pintype "passive"))
      (node (ref "D32") (pin "5") (pinfunction "CKI_5") (pintype "passive"))
    )
    (net (code "66") (name "Net-(D31-SDI)") (class "Default")
      (node (ref "D31") (pin "4") (pinfunction "SDI_4") (pintype "passive"))
      (node (ref "D39") (pin "3") (pinfunction "SDO_3") (pintype "passive"))
    )
    (net (code "67") (name "Net-(D31-SDO)") (class "Default")
      (node (ref "D31") (pin "3") (pinfunction "SDO_3") (pintype "passive"))
      (node (ref "D32") (pin "4") (pinfunction "SDI_4") (pintype "passive"))
    )
    (net (code "68") (name "Net-(D32-CKO)") (class "Default")
      (node (ref "D32") (pin "2") (pinfunction "CKO_2") (pintype "passive"))
      (node (ref "D33") (pin "5") (pinfunction "CKI_5") (pintype "passive"))
    )
    (net (code "69") (name "Net-(D32-SDO)") (class "Default")
      (node (ref "D32") (pin "3") (pinfunction "SDO_3") (pintype "passive"))
      (node (ref "D33") (pin "4") (pinfunction "SDI_4") (pintype "passive"))
    )
    (net (code "70") (name "Net-(D33-CKO)") (class "Default")
      (node (ref "D33") (pin "2") (pinfunction "CKO_2") (pintype "passive"))
      (node (ref "D34") (pin "5") (pinfunction "CKI_5") (pintype "passive"))
    )
    (net (code "71") (name "Net-(D33-SDO)") (class "Default")
      (node (ref "D33") (pin "3") (pinfunction "SDO_3") (pintype "passive"))
      (node (ref "D34") (pin "4") (pinfunction "SDI_4") (pintype "passive"))
    )
    (net (code "72") (name "Net-(D34-CKO)") (class "Default")
      (node (ref "D34") (pin "2") (pinfunction "CKO_2") (pintype "passive"))
      (node (ref "D41") (pin "5") (pinfunction "CKI_5") (pintype "passive"))
    )
    (net (code "73") (name "Net-(D34-SDO)") (class "Default")
      (node (ref "D34") (pin "3") (pinfunction "SDO_3") (pintype "passive"))
      (node (ref "D41") (pin "4") (pinfunction "SDI_4") (pintype "passive"))
    )
    (net (code "74") (name "Net-(D35-CKI)") (class "Default")
      (node (ref "D35") (pin "5") (pinfunction "CKI_5") (pintype "passive"))
      (node (ref "D36") (pin "2") (pinfunction "CKO_2") (pintype "passive"))
    )
    (net (code "75") (name "Net-(D35-CKO)") (class "Default")
      (node (ref "D35") (pin "2") (pinfunction "CKO_2") (pintype "passive"))
      (node (ref "D40") (pin "5") (pinfunction "CKI_5") (pintype "passive"))
    )
    (net (code "76") (name "Net-(D35-SDI)") (class "Default")
      (node (ref "D35") (pin "4") (pinfunction "SDI_4") (pintype "passive"))
      (node (ref "D36") (pin "3") (pinfunction "SDO_3") (pintype "passive"))
    )
    (net (code "77") (name "Net-(D35-SDO)") (class "Default")
      (node (ref "D35") (pin "3") (pinfunction "SDO_3") (pintype "passive"))
      (node (ref "D40") (pin "4") (pinfunction "SDI_4") (pintype "passive"))
    )
    (net (code "78") (name "Net-(D36-CKI)") (class "Default")
      (node (ref "D36") (pin "5") (pinfunction "CKI_5") (pintype "passive"))
      (node (ref "D37") (pin "2") (pinfunction "CKO_2") (pintype "passive"))
    )
    (net (code "79") (name "Net-(D36-SDI)") (class "Default")
      (node (ref "D36") (pin "4") (pinfunction "SDI_4") (pintype "passive"))
      (node (ref "D37") (pin "3") (pinfunction "SDO_3") (pintype "passive"))
    )
    (net (code "80") (name "Net-(D37-CKI)") (class "Default")
      (node (ref "D37") (pin "5") (pinfunction "CKI_5") (pintype "passive"))
      (node (ref "D38") (pin "2") (pinfunction "CKO_2") (pintype "passive"))
    )
    (net (code "81") (name "Net-(D37-SDI)") (class "Default")
      (node (ref "D37") (pin "4") (pinfunction "SDI_4") (pintype "passive"))
      (node (ref "D38") (pin "3") (pinfunction "SDO_3") (pintype "passive"))
    )
    (net (code "82") (name "Net-(D39-CKI)") (class "Default")
      (node (ref "D39") (pin "5") (pinfunction "CKI_5") (pintype "passive"))
      (node (ref "D40") (pin "2") (pinfunction "CKO_2") (pintype "passive"))
    )
    (net (code "83") (name "Net-(D39-SDI)") (class "Default")
      (node (ref "D39") (pin "4") (pinfunction "SDI_4") (pintype "passive"))
      (node (ref "D40") (pin "3") (pinfunction "SDO_3") (pintype "passive"))
    )
    (net (code "84") (name "Net-(D41-CKO)") (class "Default")
      (node (ref "D41") (pin "2") (pinfunction "CKO_2") (pintype "passive"))
      (node (ref "D42") (pin "5") (pinfunction "CKI_5") (pintype "passive"))
    )
    (net (code "85") (name "Net-(D41-SDO)") (class "Default")
      (node (ref "D41") (pin "3") (pinfunction "SDO_3") (pintype "passive"))
      (node (ref "D42") (pin "4") (pinfunction "SDI_4") (pintype "passive"))
    )
    (net (code "86") (name "Net-(D42-CKO)") (class "Default")
      (node (ref "D42") (pin "2") (pinfunction "CKO_2") (pintype "passive"))
      (node (ref "D43") (pin "5") (pinfunction "CKI_5") (pintype "passive"))
    )
    (net (code "87") (name "Net-(D42-SDO)") (class "Default")
      (node (ref "D42") (pin "3") (pinfunction "SDO_3") (pintype "passive"))
      (node (ref "D43") (pin "4") (pinfunction "SDI_4") (pintype "passive"))
    )
    (net (code "88") (name "Net-(D43-CKO)") (class "Default")
      (node (ref "D43") (pin "2") (pinfunction "CKO_2") (pintype "passive"))
      (node (ref "D44") (pin "5") (pinfunction "CKI_5") (pintype "passive"))
    )
    (net (code "89") (name "Net-(D43-SDO)") (class "Default")
      (node (ref "D43") (pin "3") (pinfunction "SDO_3") (pintype "passive"))
      (node (ref "D44") (pin "4") (pinfunction "SDI_4") (pintype "passive"))
    )
    (net (code "90") (name "Net-(D44-CKO)") (class "Default")
      (node (ref "D44") (pin "2") (pinfunction "CKO_2") (pintype "passive"))
      (node (ref "D45") (pin "5") (pinfunction "CKI_5") (pintype "passive"))
    )
    (net (code "91") (name "Net-(D44-SDO)") (class "Default")
      (node (ref "D44") (pin "3") (pinfunction "SDO_3") (pintype "passive"))
      (node (ref "D45") (pin "4") (pinfunction "SDI_4") (pintype "passive"))
    )
    (net (code "92") (name "Net-(D45-CKO)") (class "Default")
      (node (ref "D45") (pin "2") (pinfunction "CKO_2") (pintype "passive"))
      (node (ref "D46") (pin "5") (pinfunction "CKI_5") (pintype "passive"))
    )
    (net (code "93") (name "Net-(D45-SDO)") (class "Default")
      (node (ref "D45") (pin "3") (pinfunction "SDO_3") (pintype "passive"))
      (node (ref "D46") (pin "4") (pinfunction "SDI_4") (pintype "passive"))
    )
    (net (code "94") (name "Net-(D46-CKO)") (class "Default")
      (node (ref "D46") (pin "2") (pinfunction "CKO_2") (pintype "passive"))
      (node (ref "D47") (pin "5") (pinfunction "CKI_5") (pintype "passive"))
    )
    (net (code "95") (name "Net-(D46-SDO)") (class "Default")
      (node (ref "D46") (pin "3") (pinfunction "SDO_3") (pintype "passive"))
      (node (ref "D47") (pin "4") (pinfunction "SDI_4") (pintype "passive"))
    )
    (net (code "96") (name "Net-(D47-CKO)") (class "Default")
      (node (ref "D47") (pin "2") (pinfunction "CKO_2") (pintype "passive"))
      (node (ref "D48") (pin "5") (pinfunction "CKI_5") (pintype "passive"))
    )
    (net (code "97") (name "Net-(D47-SDO)") (class "Default")
      (node (ref "D47") (pin "3") (pinfunction "SDO_3") (pintype "passive"))
      (node (ref "D48") (pin "4") (pinfunction "SDI_4") (pintype "passive"))
    )
    (net (code "98") (name "Net-(D48-CKO)") (class "Default")
      (node (ref "D48") (pin "2") (pinfunction "CKO_2") (pintype "passive"))
      (node (ref "D49") (pin "5") (pinfunction "CKI_5") (pintype "passive"))
    )
    (net (code "99") (name "Net-(D48-SDO)") (class "Default")
      (node (ref "D48") (pin "3") (pinfunction "SDO_3") (pintype "passive"))
      (node (ref "D49") (pin "4") (pinfunction "SDI_4") (pintype "passive"))
    )
    (net (code "100") (name "Net-(D49-CKO)") (class "Default")
      (node (ref "D49") (pin "2") (pinfunction "CKO_2") (pintype "passive"))
      (node (ref "D50") (pin "5") (pinfunction "CKI_5") (pintype "passive"))
    )
    (net (code "101") (name "Net-(D49-SDO)") (class "Default")
      (node (ref "D49") (pin "3") (pinfunction "SDO_3") (pintype "passive"))
      (node (ref "D50") (pin "4") (pinfunction "SDI_4") (pintype "passive"))
    )
    (net (code "102") (name "Net-(D50-CKO)") (class "Default")
      (node (ref "D50") (pin "2") (pinfunction "CKO_2") (pintype "passive"))
      (node (ref "D51") (pin "5") (pinfunction "CKI_5") (pintype "passive"))
    )
    (net (code "103") (name "Net-(D50-SDO)") (class "Default")
      (node (ref "D50") (pin "3") (pinfunction "SDO_3") (pintype "passive"))
      (node (ref "D51") (pin "4") (pinfunction "SDI_4") (pintype "passive"))
    )
    (net (code "104") (name "Net-(D51-CKO)") (class "Default")
      (node (ref "D51") (pin "2") (pinfunction "CKO_2") (pintype "passive"))
      (node (ref "D52") (pin "5") (pinfunction "CKI_5") (pintype "passive"))
    )
    (net (code "105") (name "Net-(D51-SDO)") (class "Default")
      (node (ref "D51") (pin "3") (pinfunction "SDO_3") (pintype "passive"))
      (node (ref "D52") (pin "4") (pinfunction "SDI_4") (pintype "passive"))
    )
    (net (code "106") (name "Net-(D52-CKO)") (class "Default")
      (node (ref "D52") (pin "2") (pinfunction "CKO_2") (pintype "passive"))
      (node (ref "D53") (pin "5") (pinfunction "CKI_5") (pintype "passive"))
    )
    (net (code "107") (name "Net-(D52-SDO)") (class "Default")
      (node (ref "D52") (pin "3") (pinfunction "SDO_3") (pintype "passive"))
      (node (ref "D53") (pin "4") (pinfunction "SDI_4") (pintype "passive"))
    )
    (net (code "108") (name "Net-(D53-CKO)") (class "Default")
      (node (ref "D53") (pin "2") (pinfunction "CKO_2") (pintype "passive"))
      (node (ref "D54") (pin "5") (pinfunction "CKI_5") (pintype "passive"))
    )
    (net (code "109") (name "Net-(D53-SDO)") (class "Default")
      (node (ref "D53") (pin "3") (pinfunction "SDO_3") (pintype "passive"))
      (node (ref "D54") (pin "4") (pinfunction "SDI_4") (pintype "passive"))
    )
    (net (code "110") (name "Net-(D54-CKO)") (class "Default")
      (node (ref "D54") (pin "2") (pinfunction "CKO_2") (pintype "passive"))
      (node (ref "D55") (pin "5") (pinfunction "CKI_5") (pintype "passive"))
    )
    (net (code "111") (name "Net-(D54-SDO)") (class "Default")
      (node (ref "D54") (pin "3") (pinfunction "SDO_3") (pintype "passive"))
      (node (ref "D55") (pin "4") (pinfunction "SDI_4") (pintype "passive"))
    )
    (net (code "112") (name "Net-(D55-CKO)") (class "Default")
      (node (ref "D55") (pin "2") (pinfunction "CKO_2") (pintype "passive"))
      (node (ref "D56") (pin "5") (pinfunction "CKI_5") (pintype "passive"))
    )
    (net (code "113") (name "Net-(D55-SDO)") (class "Default")
      (node (ref "D55") (pin "3") (pinfunction "SDO_3") (pintype "passive"))
      (node (ref "D56") (pin "4") (pinfunction "SDI_4") (pintype "passive"))
    )
    (net (code "114") (name "Net-(D56-CKO)") (class "Default")
      (node (ref "D56") (pin "2") (pinfunction "CKO_2") (pintype "passive"))
      (node (ref "D61") (pin "5") (pinfunction "CKI_5") (pintype "passive"))
    )
    (net (code "115") (name "Net-(D56-SDO)") (class "Default")
      (node (ref "D56") (pin "3") (pinfunction "SDO_3") (pintype "passive"))
      (node (ref "D61") (pin "4") (pinfunction "SDI_4") (pintype "passive"))
    )
    (net (code "116") (name "Net-(D57-CKI)") (class "Default")
      (node (ref "D57") (pin "5") (pinfunction "CKI_5") (pintype "passive"))
      (node (ref "D64") (pin "2") (pinfunction "CKO_2") (pintype "passive"))
    )
    (net (code "117") (name "Net-(D57-CKO)") (class "Default")
      (node (ref "D57") (pin "2") (pinfunction "CKO_2") (pintype "passive"))
      (node (ref "D68") (pin "5") (pinfunction "CKI_5") (pintype "passive"))
    )
    (net (code "118") (name "Net-(D57-SDI)") (class "Default")
      (node (ref "D57") (pin "4") (pinfunction "SDI_4") (pintype "passive"))
      (node (ref "D64") (pin "3") (pinfunction "SDO_3") (pintype "passive"))
    )
    (net (code "119") (name "Net-(D57-SDO)") (class "Default")
      (node (ref "D57") (pin "3") (pinfunction "SDO_3") (pintype "passive"))
      (node (ref "D68") (pin "4") (pinfunction "SDI_4") (pintype "passive"))
    )
    (net (code "120") (name "Net-(D58-CKI)") (class "Default")
      (node (ref "D58") (pin "5") (pinfunction "CKI_5") (pintype "passive"))
      (node (ref "D63") (pin "2") (pinfunction "CKO_2") (pintype "passive"))
    )
    (net (code "121") (name "Net-(D58-CKO)") (class "Default")
      (node (ref "D58") (pin "2") (pinfunction "CKO_2") (pintype "passive"))
      (node (ref "D66") (pin "5") (pinfunction "CKI_5") (pintype "passive"))
    )
    (net (code "122") (name "Net-(D58-SDI)") (class "Default")
      (node (ref "D58") (pin "4") (pinfunction "SDI_4") (pintype "passive"))
      (node (ref "D63") (pin "3") (pinfunction "SDO_3") (pintype "passive"))
    )
    (net (code "123") (name "Net-(D58-SDO)") (class "Default")
      (node (ref "D58") (pin "3") (pinfunction "SDO_3") (pintype "passive"))
      (node (ref "D66") (pin "4") (pinfunction "SDI_4") (pintype "passive"))
    )
    (net (code "124") (name "Net-(D59-CKI)") (class "Default")
      (node (ref "D59") (pin "5") (pinfunction "CKI_5") (pintype "passive"))
      (node (ref "D62") (pin "2") (pinfunction "CKO_2") (pintype "passive"))
    )
    (net (code "125") (name "Net-(D59-CKO)") (class "Default")
      (node (ref "D59") (pin "2") (pinfunction "CKO_2") (pintype "passive"))
      (node (ref "D65") (pin "5") (pinfunction "CKI_5") (pintype "passive"))
    )
    (net (code "126") (name "Net-(D59-SDI)") (class "Default")
      (node (ref "D59") (pin "4") (pinfunction "SDI_4") (pintype "passive"))
      (node (ref "D62") (pin "3") (pinfunction "SDO_3") (pintype "passive"))
    )
    (net (code "127") (name "Net-(D59-SDO)") (class "Default")
      (node (ref "D59") (pin "3") (pinfunction "SDO_3") (pintype "passive"))
      (node (ref "D65") (pin "4") (pinfunction "SDI_4") (pintype "passive"))
    )
    (net (code "128") (name "Net-(D60-CKI)") (class "Default")
      (node (ref "D60") (pin "5") (pinfunction "CKI_5") (pintype "passive"))
      (node (ref "D61") (pin "2") (pinfunction "CKO_2") (pintype "passive"))
    )
    (net (code "129") (name "Net-(D60-CKO)") (class "Default")
      (node (ref "D60") (pin "2") (pinfunction "CKO_2") (pintype "passive"))
      (node (ref "D62") (pin "5") (pinfunction "CKI_5") (pintype "passive"))
    )
    (net (code "130") (name "Net-(D60-SDI)") (class "Default")
      (node (ref "D60") (pin "4") (pinfunction "SDI_4") (pintype "passive"))
      (node (ref "D61") (pin "3") (pinfunction "SDO_3") (pintype "passive"))
    )
    (net (code "131") (name "Net-(D60-SDO)") (class "Default")
      (node (ref "D60") (pin "3") (pinfunction "SDO_3") (pintype "passive"))
      (node (ref "D62") (pin "4") (pinfunction "SDI_4") (pintype "passive"))
    )
    (net (code "132") (name "Net-(D63-CKI)") (class "Default")
      (node (ref "D63") (pin "5") (pinfunction "CKI_5") (pintype "passive"))
      (node (ref "D65") (pin "2") (pinfunction "CKO_2") (pintype "passive"))
    )
    (net (code "133") (name "Net-(D63-SDI)") (class "Default")
      (node (ref "D63") (pin "4") (pinfunction "SDI_4") (pintype "passive"))
      (node (ref "D65") (pin "3") (pinfunction "SDO_3") (pintype "passive"))
    )
    (net (code "134") (name "Net-(D64-CKI)") (class "Default")
      (node (ref "D64") (pin "5") (pinfunction "CKI_5") (pintype "passive"))
      (node (ref "D67") (pin "2") (pinfunction "CKO_2") (pintype "passive"))
    )
    (net (code "135") (name "Net-(D64-SDI)") (class "Default")
      (node (ref "D64") (pin "4") (pinfunction "SDI_4") (pintype "passive"))
      (node (ref "D67") (pin "3") (pinfunction "SDO_3") (pintype "passive"))
    )
    (net (code "136") (name "Net-(D66-CKO)") (class "Default")
      (node (ref "D66") (pin "2") (pinfunction "CKO_2") (pintype "passive"))
      (node (ref "D67") (pin "5") (pinfunction "CKI_5") (pintype "passive"))
    )
    (net (code "137") (name "Net-(D66-SDO)") (class "Default")
      (node (ref "D66") (pin "3") (pinfunction "SDO_3") (pintype "passive"))
      (node (ref "D67") (pin "4") (pinfunction "SDI_4") (pintype "passive"))
    )
    (net (code "138") (name "Net-(D68-CKO)") (class "Default")
      (node (ref "D68") (pin "2") (pinfunction "CKO_2") (pintype "passive"))
      (node (ref "D69") (pin "5") (pinfunction "CKI_5") (pintype "passive"))
    )
    (net (code "139") (name "Net-(D68-SDO)") (class "Default")
      (node (ref "D68") (pin "3") (pinfunction "SDO_3") (pintype "passive"))
      (node (ref "D69") (pin "4") (pinfunction "SDI_4") (pintype "passive"))
    )
    (net (code "140") (name "Net-(D69-CKO)") (class "Default")
      (node (ref "D69") (pin "2") (pinfunction "CKO_2") (pintype "passive"))
      (node (ref "D70") (pin "5") (pinfunction "CKI_5") (pintype "passive"))
    )
    (net (code "141") (name "Net-(D69-SDO)") (class "Default")
      (node (ref "D69") (pin "3") (pinfunction "SDO_3") (pintype "passive"))
      (node (ref "D70") (pin "4") (pinfunction "SDI_4") (pintype "passive"))
    )
    (net (code "142") (name "Net-(D70-CKO)") (class "Default")
      (node (ref "D70") (pin "2") (pinfunction "CKO_2") (pintype "passive"))
      (node (ref "D71") (pin "5") (pinfunction "CKI_5") (pintype "passive"))
    )
    (net (code "143") (name "Net-(D70-SDO)") (class "Default")
      (node (ref "D70") (pin "3") (pinfunction "SDO_3") (pintype "passive"))
      (node (ref "D71") (pin "4") (pinfunction "SDI_4") (pintype "passive"))
    )
    (net (code "144") (name "Net-(D71-CKO)") (class "Default")
      (node (ref "D71") (pin "2") (pinfunction "CKO_2") (pintype "passive"))
      (node (ref "D72") (pin "5") (pinfunction "CKI_5") (pintype "passive"))
    )
    (net (code "145") (name "Net-(D71-SDO)") (class "Default")
      (node (ref "D71") (pin "3") (pinfunction "SDO_3") (pintype "passive"))
      (node (ref "D72") (pin "4") (pinfunction "SDI_4") (pintype "passive"))
    )
    (net (code "146") (name "Net-(D72-CKO)") (class "Default")
      (node (ref "D72") (pin "2") (pinfunction "CKO_2") (pintype "passive"))
      (node (ref "D73") (pin "5") (pinfunction "CKI_5") (pintype "passive"))
    )
    (net (code "147") (name "Net-(D72-SDO)") (class "Default")
      (node (ref "D72") (pin "3") (pinfunction "SDO_3") (pintype "passive"))
      (node (ref "D73") (pin "4") (pinfunction "SDI_4") (pintype "passive"))
    )
    (net (code "148") (name "Net-(D73-CKO)") (class "Default")
      (node (ref "D73") (pin "2") (pinfunction "CKO_2") (pintype "passive"))
      (node (ref "D74") (pin "5") (pinfunction "CKI_5") (pintype "passive"))
    )
    (net (code "149") (name "Net-(D73-SDO)") (class "Default")
      (node (ref "D73") (pin "3") (pinfunction "SDO_3") (pintype "passive"))
      (node (ref "D74") (pin "4") (pinfunction "SDI_4") (pintype "passive"))
    )
    (net (code "150") (name "Net-(D74-CKO)") (class "Default")
      (node (ref "D74") (pin "2") (pinfunction "CKO_2") (pintype "passive"))
      (node (ref "D75") (pin "5") (pinfunction "CKI_5") (pintype "passive"))
    )
    (net (code "151") (name "Net-(D74-SDO)") (class "Default")
      (node (ref "D74") (pin "3") (pinfunction "SDO_3") (pintype "passive"))
      (node (ref "D75") (pin "4") (pinfunction "SDI_4") (pintype "passive"))
    )
    (net (code "152") (name "Net-(D75-CKO)") (class "Default")
      (node (ref "D75") (pin "2") (pinfunction "CKO_2") (pintype "passive"))
      (node (ref "D76") (pin "5") (pinfunction "CKI_5") (pintype "passive"))
    )
    (net (code "153") (name "Net-(D75-SDO)") (class "Default")
      (node (ref "D75") (pin "3") (pinfunction "SDO_3") (pintype "passive"))
      (node (ref "D76") (pin "4") (pinfunction "SDI_4") (pintype "passive"))
    )
    (net (code "154") (name "Net-(D76-CKO)") (class "Default")
      (node (ref "D76") (pin "2") (pinfunction "CKO_2") (pintype "passive"))
      (node (ref "D77") (pin "5") (pinfunction "CKI_5") (pintype "passive"))
    )
    (net (code "155") (name "Net-(D76-SDO)") (class "Default")
      (node (ref "D76") (pin "3") (pinfunction "SDO_3") (pintype "passive"))
      (node (ref "D77") (pin "4") (pinfunction "SDI_4") (pintype "passive"))
    )
    (net (code "156") (name "Net-(D77-CKO)") (class "Default")
      (node (ref "D77") (pin "2") (pinfunction "CKO_2") (pintype "passive"))
      (node (ref "D78") (pin "5") (pinfunction "CKI_5") (pintype "passive"))
    )
    (net (code "157") (name "Net-(D77-SDO)") (class "Default")
      (node (ref "D77") (pin "3") (pinfunction "SDO_3") (pintype "passive"))
      (node (ref "D78") (pin "4") (pinfunction "SDI_4") (pintype "passive"))
    )
    (net (code "158") (name "Net-(D78-CKO)") (class "Default")
      (node (ref "D78") (pin "2") (pinfunction "CKO_2") (pintype "passive"))
      (node (ref "D79") (pin "5") (pinfunction "CKI_5") (pintype "passive"))
    )
    (net (code "159") (name "Net-(D78-SDO)") (class "Default")
      (node (ref "D78") (pin "3") (pinfunction "SDO_3") (pintype "passive"))
      (node (ref "D79") (pin "4") (pinfunction "SDI_4") (pintype "passive"))
    )
    (net (code "160") (name "Net-(D79-CKO)") (class "Default")
      (node (ref "D79") (pin "2") (pinfunction "CKO_2") (pintype "passive"))
      (node (ref "D80") (pin "5") (pinfunction "CKI_5") (pintype "passive"))
    )
    (net (code "161") (name "Net-(D79-SDO)") (class "Default")
      (node (ref "D79") (pin "3") (pinfunction "SDO_3") (pintype "passive"))
      (node (ref "D80") (pin "4") (pinfunction "SDI_4") (pintype "passive"))
    )
    (net (code "162") (name "Net-(D80-CKO)") (class "Default")
      (node (ref "D80") (pin "2") (pinfunction "CKO_2") (pintype "passive"))
      (node (ref "D81") (pin "5") (pinfunction "CKI_5") (pintype "passive"))
    )
    (net (code "163") (name "Net-(D80-SDO)") (class "Default")
      (node (ref "D80") (pin "3") (pinfunction "SDO_3") (pintype "passive"))
      (node (ref "D81") (pin "4") (pinfunction "SDI_4") (pintype "passive"))
    )
    (net (code "164") (name "Net-(D81-CKO)") (class "Default")
      (node (ref "D81") (pin "2") (pinfunction "CKO_2") (pintype "passive"))
      (node (ref "D82") (pin "5") (pinfunction "CKI_5") (pintype "passive"))
    )
    (net (code "165") (name "Net-(D81-SDO)") (class "Default")
      (node (ref "D81") (pin "3") (pinfunction "SDO_3") (pintype "passive"))
      (node (ref "D82") (pin "4") (pinfunction "SDI_4") (pintype "passive"))
    )
    (net (code "166") (name "Net-(D82-CKO)") (class "Default")
      (node (ref "D82") (pin "2") (pinfunction "CKO_2") (pintype "passive"))
      (node (ref "D83") (pin "5") (pinfunction "CKI_5") (pintype "passive"))
    )
    (net (code "167") (name "Net-(D82-SDO)") (class "Default")
      (node (ref "D82") (pin "3") (pinfunction "SDO_3") (pintype "passive"))
      (node (ref "D83") (pin "4") (pinfunction "SDI_4") (pintype "passive"))
    )
    (net (code "168") (name "VDD") (class "Default")
      (node (ref "C11") (pin "2") (pinfunction "2_2") (pintype "passive"))
      (node (ref "C12") (pin "2") (pinfunction "2_2") (pintype "passive"))
      (node (ref "C13") (pin "2") (pinfunction "2_2") (pintype "passive"))
      (node (ref "C14") (pin "2") (pinfunction "2_2") (pintype "passive"))
      (node (ref "C15") (pin "2") (pinfunction "2_2") (pintype "passive"))
      (node (ref "C16") (pin "2") (pinfunction "2_2") (pintype "passive"))
      (node (ref "C17") (pin "2") (pinfunction "2_2") (pintype "passive"))
      (node (ref "C18") (pin "2") (pinfunction "2_2") (pintype "passive"))
      (node (ref "C19") (pin "2") (pinfunction "2_2") (pintype "passive"))
      (node (ref "C20") (pin "2") (pinfunction "2_2") (pintype "passive"))
      (node (ref "C21") (pin "2") (pinfunction "2_2") (pintype "passive"))
      (node (ref "C22") (pin "2") (pinfunction "2_2") (pintype "passive"))
      (node (ref "D1") (pin "1") (pinfunction "VDD_1") (pintype "passive"))
      (node (ref "D10") (pin "1") (pinfunction "VDD_1") (pintype "passive"))
      (node (ref "D11") (pin "1") (pinfunction "VDD_1") (pintype "passive"))
      (node (ref "D12") (pin "1") (pinfunction "VDD_1") (pintype "passive"))
      (node (ref "D13") (pin "1") (pinfunction "VDD_1") (pintype "passive"))
      (node (ref "D14") (pin "1") (pinfunction "VDD_1") (pintype "passive"))
      (node (ref "D15") (pin "1") (pinfunction "VDD_1") (pintype "passive"))
      (node (ref "D16") (pin "1") (pinfunction "VDD_1") (pintype "passive"))
      (node (ref "D17") (pin "1") (pinfunction "VDD_1") (pintype "passive"))
      (node (ref "D18") (pin "1") (pinfunction "VDD_1") (pintype "passive"))
      (node (ref "D19") (pin "1") (pinfunction "VDD_1") (pintype "passive"))
      (node (ref "D2") (pin "1") (pinfunction "VDD_1") (pintype "passive"))
      (node (ref "D20") (pin "1") (pinfunction "VDD_1") (pintype "passive"))
      (node (ref "D21") (pin "1") (pinfunction "VDD_1") (pintype "passive"))
      (node (ref "D22") (pin "1") (pinfunction "VDD_1") (pintype "passive"))
      (node (ref "D23") (pin "1") (pinfunction "VDD_1") (pintype "passive"))
      (node (ref "D24") (pin "1") (pinfunction "VDD_1") (pintype "passive"))
      (node (ref "D25") (pin "1") (pinfunction "VDD_1") (pintype "passive"))
      (node (ref "D26") (pin "1") (pinfunction "VDD_1") (pintype "passive"))
      (node (ref "D27") (pin "1") (pinfunction "VDD_1") (pintype "passive"))
      (node (ref "D28") (pin "1") (pinfunction "VDD_1") (pintype "passive"))
      (node (ref "D29") (pin "1") (pinfunction "VDD_1") (pintype "passive"))
      (node (ref "D3") (pin "1") (pinfunction "VDD_1") (pintype "passive"))
      (node (ref "D30") (pin "1") (pinfunction "VDD_1") (pintype "passive"))
      (node (ref "D31") (pin "1") (pinfunction "VDD_1") (pintype "passive"))
      (node (ref "D32") (pin "1") (pinfunction "VDD_1") (pintype "passive"))
      (node (ref "D33") (pin "1") (pinfunction "VDD_1") (pintype "passive"))
      (node (ref "D34") (pin "1") (pinfunction "VDD_1") (pintype "passive"))
      (node (ref "D35") (pin "1") (pinfunction "VDD_1") (pintype "passive"))
      (node (ref "D36") (pin "1") (pinfunction "VDD_1") (pintype "passive"))
      (node (ref "D37") (pin "1") (pinfunction "VDD_1") (pintype "passive"))
      (node (ref "D38") (pin "1") (pinfunction "VDD_1") (pintype "passive"))
      (node (ref "D39") (pin "1") (pinfunction "VDD_1") (pintype "passive"))
      (node (ref "D4") (pin "1") (pinfunction "VDD_1") (pintype "passive"))
      (node (ref "D40") (pin "1") (pinfunction "VDD_1") (pintype "passive"))
      (node (ref "D41") (pin "1") (pinfunction "VDD_1") (pintype "passive"))
      (node (ref "D42") (pin "1") (pinfunction "VDD_1") (pintype "passive"))
      (node (ref "D43") (pin "1") (pinfunction "VDD_1") (pintype "passive"))
      (node (ref "D44") (pin "1") (pinfunction "VDD_1") (pintype "passive"))
      (node (ref "D45") (pin "1") (pinfunction "VDD_1") (pintype "passive"))
      (node (ref "D46") (pin "1") (pinfunction "VDD_1") (pintype "passive"))
      (node (ref "D47") (pin "1") (pinfunction "VDD_1") (pintype "passive"))
      (node (ref "D48") (pin "1") (pinfunction "VDD_1") (pintype "passive"))
      (node (ref "D49") (pin "1") (pinfunction "VDD_1") (pintype "passive"))
      (node (ref "D5") (pin "1") (pinfunction "VDD_1") (pintype "passive"))
      (node (ref "D50") (pin "1") (pinfunction "VDD_1") (pintype "passive"))
      (node (ref "D51") (pin "1") (pinfunction "VDD_1") (pintype "passive"))
      (node (ref "D52") (pin "1") (pinfunction "VDD_1") (pintype "passive"))
      (node (ref "D53") (pin "1") (pinfunction "VDD_1") (pintype "passive"))
      (node (ref "D54") (pin "1") (pinfunction "VDD_1") (pintype "passive"))
      (node (ref "D55") (pin "1") (pinfunction "VDD_1") (pintype "passive"))
      (node (ref "D56") (pin "1") (pinfunction "VDD_1") (pintype "passive"))
      (node (ref "D57") (pin "1") (pinfunction "VDD_1") (pintype "passive"))
      (node (ref "D58") (pin "1") (pinfunction "VDD_1") (pintype "passive"))
      (node (ref "D59") (pin "1") (pinfunction "VDD_1") (pintype "passive"))
      (node (ref "D6") (pin "1") (pinfunction "VDD_1") (pintype "passive"))
      (node (ref "D60") (pin "1") (pinfunction "VDD_1") (pintype "passive"))
      (node (ref "D61") (pin "1") (pinfunction "VDD_1") (pintype "passive"))
      (node (ref "D62") (pin "1") (pinfunction "VDD_1") (pintype "passive"))
      (node (ref "D63") (pin "1") (pinfunction "VDD_1") (pintype "passive"))
      (node (ref "D64") (pin "1") (pinfunction "VDD_1") (pintype "passive"))
      (node (ref "D65") (pin "1") (pinfunction "VDD_1") (pintype "passive"))
      (node (ref "D66") (pin "1") (pinfunction "VDD_1") (pintype "passive"))
      (node (ref "D67") (pin "1") (pinfunction "VDD_1") (pintype "passive"))
      (node (ref "D68") (pin "1") (pinfunction "VDD_1") (pintype "passive"))
      (node (ref "D69") (pin "1") (pinfunction "VDD_1") (pintype "passive"))
      (node (ref "D7") (pin "1") (pinfunction "VDD_1") (pintype "passive"))
      (node (ref "D70") (pin "1") (pinfunction "VDD_1") (pintype "passive"))
      (node (ref "D71") (pin "1") (pinfunction "VDD_1") (pintype "passive"))
      (node (ref "D72") (pin "1") (pinfunction "VDD_1") (pintype "passive"))
      (node (ref "D73") (pin "1") (pinfunction "VDD_1") (pintype "passive"))
      (node (ref "D74") (pin "1") (pinfunction "VDD_1") (pintype "passive"))
      (node (ref "D75") (pin "1") (pinfunction "VDD_1") (pintype "passive"))
      (node (ref "D76") (pin "1") (pinfunction "VDD_1") (pintype "passive"))
      (node (ref "D77") (pin "1") (pinfunction "VDD_1") (pintype "passive"))
      (node (ref "D78") (pin "1") (pinfunction "VDD_1") (pintype "passive"))
      (node (ref "D79") (pin "1") (pinfunction "VDD_1") (pintype "passive"))
      (node (ref "D8") (pin "1") (pinfunction "VDD_1") (pintype "passive"))
      (node (ref "D80") (pin "1") (pinfunction "VDD_1") (pintype "passive"))
      (node (ref "D81") (pin "1") (pinfunction "VDD_1") (pintype "passive"))
      (node (ref "D82") (pin "1") (pinfunction "VDD_1") (pintype "passive"))
      (node (ref "D83") (pin "1") (pinfunction "VDD_1") (pintype "passive"))
      (node (ref "D9") (pin "1") (pinfunction "VDD_1") (pintype "passive"))
    )
    (net (code "169") (name "unconnected-(D17-CKO-Pad2)") (class "Default")
      (node (ref "D17") (pin "2") (pinfunction "CKO_2") (pintype "passive"))
    )
    (net (code "170") (name "unconnected-(D17-SDO-Pad3)") (class "Default")
      (node (ref "D17") (pin "3") (pinfunction "SDO_3") (pintype "passive"))
    )
  )
)
